# Power_Supply.net
KiCad netlist of a schematic drawn in EAGLE
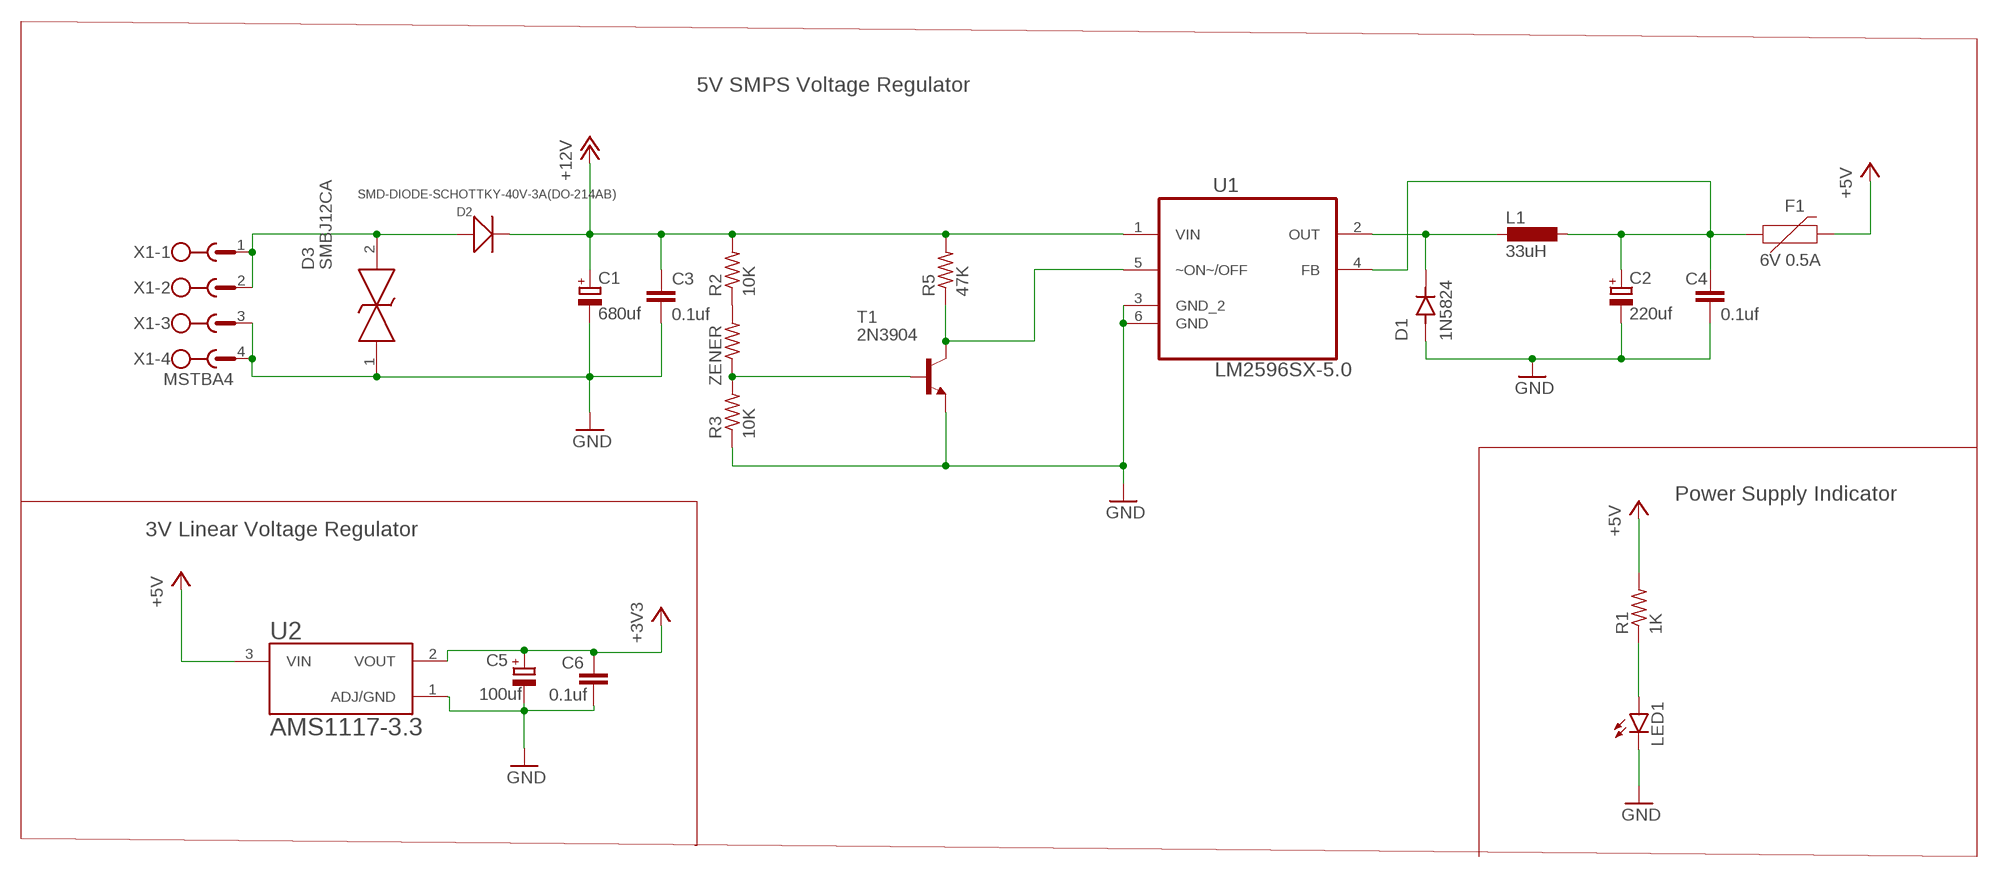
[diagram p0: schematic, sheet 1]

(export (version "E")
  (design (tool "Eeschema 10.0.6"))
  (components
    (comp (ref "C1")
      (value "680uf")
      (footprint "eagle-import:SMC_B")
      (libsource (lib "eagle-import") (part "CPOL-EUSMCB"))
    )
    (comp (ref "C2")
      (value "220uf")
      (footprint "eagle-import:SMC_B")
      (libsource (lib "eagle-import") (part "CPOL-EUSMCB"))
    )
    (comp (ref "C3")
      (value "0.1uf")
      (footprint "eagle-import:C0805")
      (libsource (lib "eagle-import") (part "C-EUC0805"))
    )
    (comp (ref "C4")
      (value "0.1uf")
      (footprint "eagle-import:C0805")
      (libsource (lib "eagle-import") (part "C-EUC0805"))
    )
    (comp (ref "C5")
      (value "100uf")
      (footprint "eagle-import:SMC_B")
      (libsource (lib "eagle-import") (part "CPOL-EUSMCB"))
    )
    (comp (ref "C6")
      (value "0.1uf")
      (footprint "eagle-import:C0805")
      (libsource (lib "eagle-import") (part "C-EUC0805"))
    )
    (comp (ref "D1")
      (value "1N5824")
      (footprint "eagle-import:DIOAD1898W129L762D1143")
      (fields (field (name "MF") "Microchip Technology"))
      (libsource (lib "eagle-import") (part "1N5824"))
    )
    (comp (ref "D2")
      (value "SMD-DIODE-SCHOTTKY-40V-3A(DO-214AB)")
      (footprint "eagle-import:DO-214AB")
      (fields (field (name "MF") "Vishay") (field (name "MP") "SS34-E3/57T"))
      (libsource (lib "eagle-import") (part "SMD-DIODE-SCHOTTKY-40V-3A(DO-214AB)"))
    )
    (comp (ref "D3")
      (value "SMBJ12CA")
      (footprint "eagle-import:DIONM5443X244N")
      (fields (field (name "MOUSER_PART_NUMBER") "652-SMBJ12CA"))
      (libsource (lib "eagle-import") (part "SMBJ12CA"))
    )
    (comp (ref "F1")
      (value "6V 0.5A")
      (footprint "eagle-import:0805")
      (libsource (lib "eagle-import") (part "PPTC_6V500MA"))
    )
    (comp (ref "L1")
      (value "33uH")
      (footprint "eagle-import:L1812")
      (libsource (lib "eagle-import") (part "L-EUL1812"))
    )
    (comp (ref "LED1")
      (value "LED3MM")
      (footprint "eagle-import:LED3MM")
      (libsource (lib "eagle-import") (part "LED3MM"))
    )
    (comp (ref "R1")
      (value "1K")
      (footprint "eagle-import:R0805")
      (libsource (lib "eagle-import") (part "R-US_R0805"))
    )
    (comp (ref "R2")
      (value "10K")
      (footprint "eagle-import:R0805")
      (libsource (lib "eagle-import") (part "R-US_R0805"))
    )
    (comp (ref "R3")
      (value "10K")
      (footprint "eagle-import:R0805")
      (libsource (lib "eagle-import") (part "R-US_R0805"))
    )
    (comp (ref "R5")
      (value "47K")
      (footprint "eagle-import:0204_7")
      (libsource (lib "eagle-import") (part "R-US_0204/7"))
    )
    (comp (ref "T1")
      (value "2N3904")
      (footprint "eagle-import:TO92")
      (libsource (lib "eagle-import") (part "2N3904"))
    )
    (comp (ref "U1")
      (value "LM2596SX-5.0")
      (footprint "eagle-import:TO170P1435X465-6N")
      (fields (field (name "MF") "Texas Instruments"))
      (libsource (lib "eagle-import") (part "LM2596SX-5.0"))
    )
    (comp (ref "U2")
      (value "AMS1117-3.3")
      (footprint "eagle-import:SOT229P700X180-4N")
      (fields (field (name "MF") "Advanced Monolithic Systems"))
      (libsource (lib "eagle-import") (part "AMS1117-3.3"))
    )
    (comp (ref "X1")
      (value "MSTBA4")
      (footprint "eagle-import:MSTBA4")
      (fields (field (name "MF") "FARNELL") (field (name "MPN") "1757268"))
      (libsource (lib "eagle-import") (part "MSTBA4"))
    )
    (comp (ref "ZENER")
      (value "R-US_0204/7")
      (footprint "eagle-import:0204_7")
      (libsource (lib "eagle-import") (part "R-US_0204/7"))
    )
  )
  (nets
    (net (code "1") (name "+3V3") (class "Default")
      (node (ref "C5") (pin "+") (pinfunction "+_+") (pintype "passive"))
      (node (ref "C6") (pin "1") (pinfunction "1_1") (pintype "passive"))
      (node (ref "U2") (pin "2") (pinfunction "VOUT_2") (pintype "output"))
    )
    (net (code "2") (name "+5V") (class "Default")
      (node (ref "F1") (pin "2") (pinfunction "2_2") (pintype "bidirectional"))
      (node (ref "R1") (pin "2") (pinfunction "2_2") (pintype "passive"))
      (node (ref "U2") (pin "3") (pinfunction "VIN_3") (pintype "input"))
    )
    (net (code "3") (name "+12V") (class "Default")
      (node (ref "C1") (pin "+") (pinfunction "+_+") (pintype "passive"))
      (node (ref "C3") (pin "1") (pinfunction "1_1") (pintype "passive"))
      (node (ref "D2") (pin "2") (pinfunction "-_2") (pintype "passive"))
      (node (ref "R2") (pin "2") (pinfunction "2_2") (pintype "passive"))
      (node (ref "R5") (pin "2") (pinfunction "2_2") (pintype "passive"))
      (node (ref "U1") (pin "1") (pinfunction "VIN_1") (pintype "input"))
    )
    (net (code "4") (name "GND") (class "Default")
      (node (ref "C1") (pin "-") (pinfunction "-_-") (pintype "passive"))
      (node (ref "C2") (pin "-") (pinfunction "-_-") (pintype "passive"))
      (node (ref "C3") (pin "2") (pinfunction "2_2") (pintype "passive"))
      (node (ref "C4") (pin "2") (pinfunction "2_2") (pintype "passive"))
      (node (ref "C5") (pin "-") (pinfunction "-_-") (pintype "passive"))
      (node (ref "C6") (pin "2") (pinfunction "2_2") (pintype "passive"))
      (node (ref "D1") (pin "A") (pinfunction "A_A") (pintype "passive"))
      (node (ref "D3") (pin "1") (pinfunction "1_1") (pintype "bidirectional"))
      (node (ref "LED1") (pin "K") (pinfunction "C_K") (pintype "passive"))
      (node (ref "R3") (pin "1") (pinfunction "1_1") (pintype "passive"))
      (node (ref "T1") (pin "3") (pinfunction "E_3") (pintype "passive"))
      (node (ref "U1") (pin "3") (pinfunction "GND_2_3") (pintype "passive"))
      (node (ref "U1") (pin "6") (pinfunction "GND_6") (pintype "passive"))
      (node (ref "U2") (pin "1") (pinfunction "ADJ/GND_1") (pintype "power_in"))
      (node (ref "X1") (pin "3") (pinfunction "1_3") (pintype "passive"))
      (node (ref "X1") (pin "4") (pinfunction "1_4") (pintype "passive"))
    )
    (net (code "5") (name "Net-(D1-K)") (class "Default")
      (node (ref "D1") (pin "C") (pinfunction "K_C") (pintype "passive"))
      (node (ref "L1") (pin "2") (pinfunction "2_2") (pintype "passive"))
      (node (ref "U1") (pin "2") (pinfunction "OUT_2") (pintype "output"))
    )
    (net (code "6") (name "Net-(D2-+)") (class "Default")
      (node (ref "D2") (pin "1") (pinfunction "+_1") (pintype "passive"))
      (node (ref "D3") (pin "2") (pinfunction "2_2") (pintype "bidirectional"))
      (node (ref "X1") (pin "1") (pinfunction "1_1") (pintype "passive"))
      (node (ref "X1") (pin "2") (pinfunction "1_2") (pintype "passive"))
    )
    (net (code "7") (name "Net-(LED1-PadA)") (class "Default")
      (node (ref "LED1") (pin "A") (pinfunction "A_A") (pintype "passive"))
      (node (ref "R1") (pin "1") (pinfunction "1_1") (pintype "passive"))
    )
    (net (code "8") (name "Net-(R2-Pad1)") (class "Default")
      (node (ref "R2") (pin "1") (pinfunction "1_1") (pintype "passive"))
      (node (ref "ZENER") (pin "2") (pinfunction "2_2") (pintype "passive"))
    )
    (net (code "9") (name "Net-(T1-B)") (class "Default")
      (node (ref "R3") (pin "2") (pinfunction "2_2") (pintype "passive"))
      (node (ref "T1") (pin "2") (pinfunction "B_2") (pintype "passive"))
      (node (ref "ZENER") (pin "1") (pinfunction "1_1") (pintype "passive"))
    )
    (net (code "10") (name "Net-(T1-C)") (class "Default")
      (node (ref "R5") (pin "1") (pinfunction "1_1") (pintype "passive"))
      (node (ref "T1") (pin "1") (pinfunction "C_1") (pintype "passive"))
      (node (ref "U1") (pin "5") (pinfunction "~{ON}/OFF_5") (pintype "passive"))
    )
    (net (code "11") (name "Net-(U1-FB)") (class "Default")
      (node (ref "C2") (pin "+") (pinfunction "+_+") (pintype "passive"))
      (node (ref "C4") (pin "1") (pinfunction "1_1") (pintype "passive"))
      (node (ref "F1") (pin "1") (pinfunction "1_1") (pintype "bidirectional"))
      (node (ref "L1") (pin "1") (pinfunction "1_1") (pintype "passive"))
      (node (ref "U1") (pin "4") (pinfunction "FB_4") (pintype "bidirectional"))
    )
  )
)
